# Wifi.net
KiCad netlist of a schematic drawn in Altium Designer
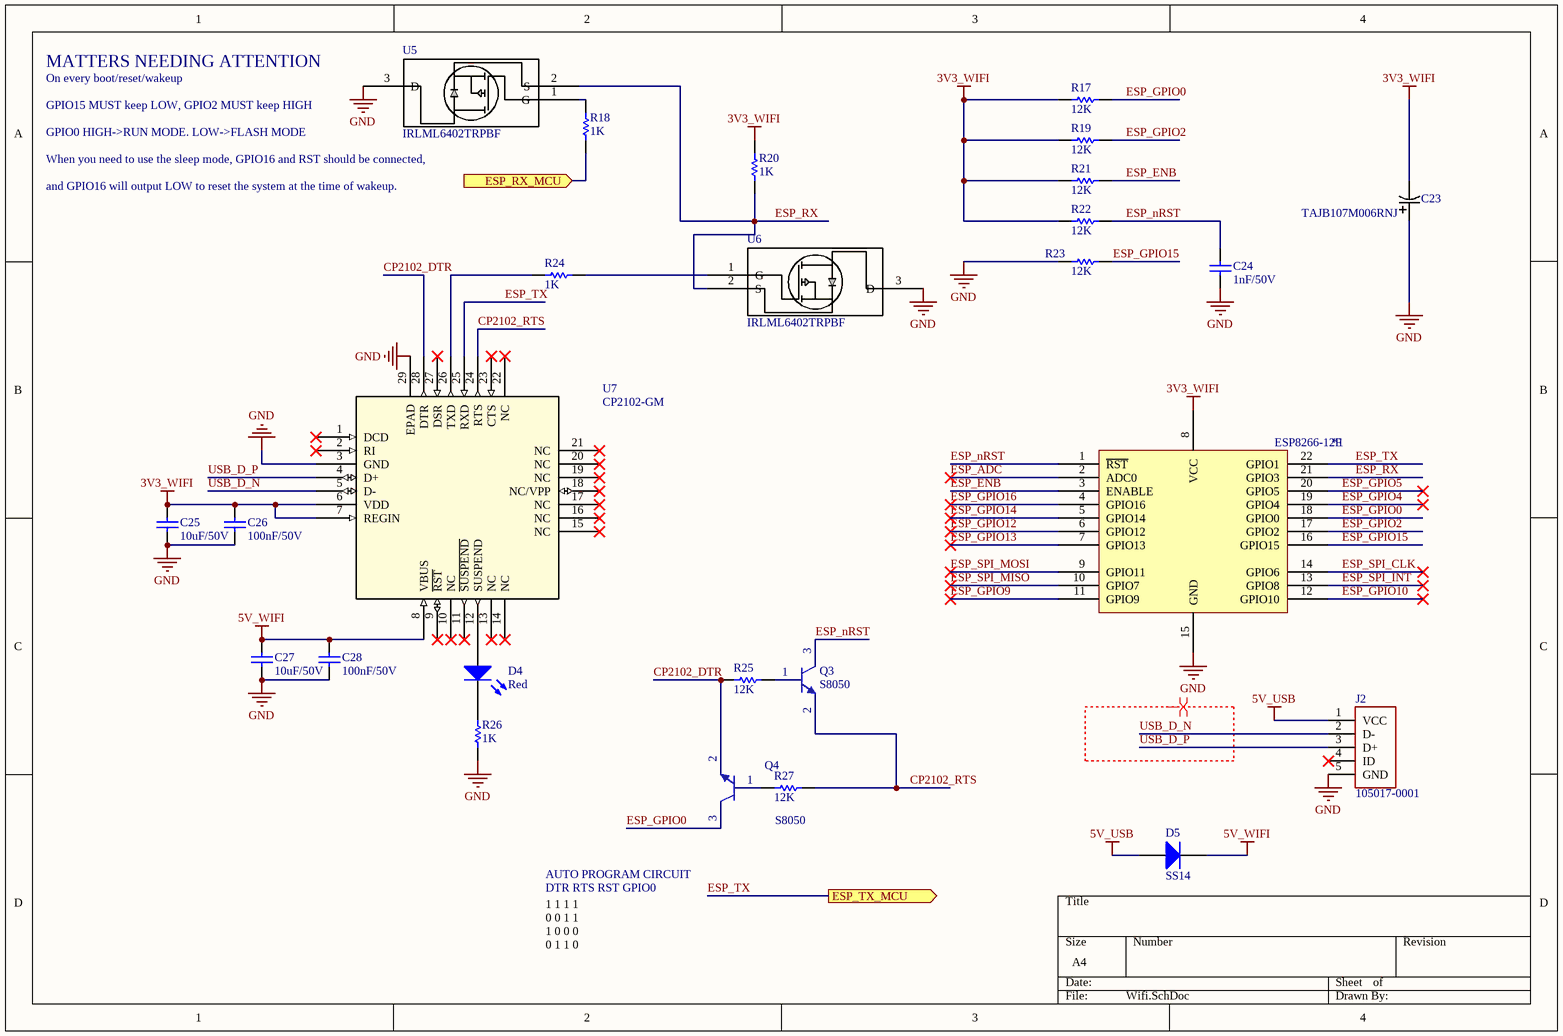
[diagram p0: Wifi.SchDoc]

(export (version "E")
  (design (tool "Eeschema 10.0.6"))
  (components
    (comp (ref "*1")
      (value "ESP8266-12F")
      (footprint "ESP8266")
      (libsource (lib "Schlib1") (part "ESP8266-12F"))
    )
    (comp (ref "C23")
      (value "TAJB107M006RNJ")
      (footprint "TAJB107M006RNJ")
      (fields (field (name "COPYRIGHT") "Copyright (C) 2018 Accelerated Designs. All rights reserved"))
      (libsource (lib "Integrated_Library") (part "TAJB107M006RNJ"))
    )
    (comp (ref "C24")
      (value "1nF/50V")
      (footprint "CAP-SM-0805")
      (description "CAP CER 1000PF 100V X7R 0805")
      (fields
        (field (name "MANUFACTURER") "Johanson Dielectrics Inc.")
        (field (name "MANUFACTURER PART NUMBER") "101X15W102MV4E")
      )
      (libsource (lib "Capacitor") (part "Cap-1nF-50V-0805"))
    )
    (comp (ref "C25")
      (value "10uF/50V")
      (footprint "CAP-SM-0805")
      (description "CAP CER 1000PF 100V X7R 0805")
      (fields
        (field (name "MANUFACTURER") "Johanson Dielectrics Inc.")
        (field (name "MANUFACTURER PART NUMBER") "101X15W102MV4E")
      )
      (libsource (lib "Capacitor") (part "Cap-1nF-50V-0805"))
    )
    (comp (ref "C26")
      (value "100nF/50V")
      (footprint "CAP-SM-0805")
      (description "CAP CER 1000PF 100V X7R 0805")
      (fields
        (field (name "MANUFACTURER") "Johanson Dielectrics Inc.")
        (field (name "MANUFACTURER PART NUMBER") "101X15W102MV4E")
      )
      (libsource (lib "Capacitor") (part "Cap-1nF-50V-0805"))
    )
    (comp (ref "C27")
      (value "10uF/50V")
      (footprint "CAP-SM-0805")
      (description "CAP CER 1000PF 100V X7R 0805")
      (fields
        (field (name "MANUFACTURER") "Johanson Dielectrics Inc.")
        (field (name "MANUFACTURER PART NUMBER") "101X15W102MV4E")
      )
      (libsource (lib "Capacitor") (part "Cap-1nF-50V-0805"))
    )
    (comp (ref "C28")
      (value "100nF/50V")
      (footprint "CAP-SM-0805")
      (description "CAP CER 1000PF 100V X7R 0805")
      (fields
        (field (name "MANUFACTURER") "Johanson Dielectrics Inc.")
        (field (name "MANUFACTURER PART NUMBER") "101X15W102MV4E")
      )
      (libsource (lib "Capacitor") (part "Cap-1nF-50V-0805"))
    )
    (comp (ref "D4")
      (value "Red")
      (footprint "LED-3mm")
      (description "LED RED CLEAR T-1 T/H")
      (fields
        (field (name "MANUFACTURER") "Kingbright")
        (field (name "MANUFACTURER PART NUMBER") "WP710A10SEC/J3")
      )
      (libsource (lib "LED") (part "LED-RED-TH-3mm"))
    )
    (comp (ref "D5")
      (value "SS14")
      (footprint "SS14")
      (description "DIODE SCHOTTKY 40V 1A SMA")
      (fields (field (name "MANUFACTURER") "ON Semiconductor"))
      (libsource (lib "Diode") (part "Diode-SS14"))
    )
    (comp (ref "J2")
      (value "105017-0001")
      (footprint "CONN_105017-0001")
      (description "No Description Available")
      (fields (field (name "COPYRIGHT") "Copyright (C) 2018 Accelerated Designs. All rights reserved"))
      (libsource (lib "Header-connector") (part "105017-0001"))
    )
    (comp (ref "Q3") (value "S8050") (footprint "SOT23_NEX") (libsource (lib "BJT") (part "S8050")))
    (comp (ref "Q4") (value "S8050") (footprint "SOT23_NEX") (libsource (lib "BJT") (part "S8050")))
    (comp (ref "R17")
      (value "12K")
      (footprint "Resistor:RES-SM-0805")
      (description "RES 0 OHM JUMPER 0805")
      (fields
        (field (name "MANUFACTURER") "Vishay Dale")
        (field (name "MANUFACTURER PART NUMBER") "WSL080500000ZEA9")
      )
      (libsource (lib "Resistor") (part "Res-0-0805"))
    )
    (comp (ref "R18")
      (value "1K")
      (footprint "Resistor:RES-SM-0805")
      (description "RES 470 OHM JUMPER 0805")
      (fields
        (field (name "MANUFACTURER") "YAG6006CT-ND")
        (field (name "MANUFACTURER PART NUMBER") "PE0805FRF7W0R047L")
      )
      (libsource (lib "Resistor") (part "Res-470-0805"))
    )
    (comp (ref "R19")
      (value "12K")
      (footprint "Resistor:RES-SM-0805")
      (description "RES 0 OHM JUMPER 0805")
      (fields
        (field (name "MANUFACTURER") "Vishay Dale")
        (field (name "MANUFACTURER PART NUMBER") "WSL080500000ZEA9")
      )
      (libsource (lib "Resistor") (part "Res-0-0805"))
    )
    (comp (ref "R20")
      (value "1K")
      (footprint "Resistor:RES-SM-0805")
      (description "RES 470 OHM JUMPER 0805")
      (fields
        (field (name "MANUFACTURER") "YAG6006CT-ND")
        (field (name "MANUFACTURER PART NUMBER") "PE0805FRF7W0R047L")
      )
      (libsource (lib "Resistor") (part "Res-470-0805"))
    )
    (comp (ref "R21")
      (value "12K")
      (footprint "Resistor:RES-SM-0805")
      (description "RES 0 OHM JUMPER 0805")
      (fields
        (field (name "MANUFACTURER") "Vishay Dale")
        (field (name "MANUFACTURER PART NUMBER") "WSL080500000ZEA9")
      )
      (libsource (lib "Resistor") (part "Res-0-0805"))
    )
    (comp (ref "R22")
      (value "12K")
      (footprint "Resistor:RES-SM-0805")
      (description "RES 0 OHM JUMPER 0805")
      (fields
        (field (name "MANUFACTURER") "Vishay Dale")
        (field (name "MANUFACTURER PART NUMBER") "WSL080500000ZEA9")
      )
      (libsource (lib "Resistor") (part "Res-0-0805"))
    )
    (comp (ref "R23")
      (value "12K")
      (footprint "Resistor:RES-SM-0805")
      (description "RES 0 OHM JUMPER 0805")
      (fields
        (field (name "MANUFACTURER") "Vishay Dale")
        (field (name "MANUFACTURER PART NUMBER") "WSL080500000ZEA9")
      )
      (libsource (lib "Resistor") (part "Res-0-0805"))
    )
    (comp (ref "R24")
      (value "1K")
      (footprint "Resistor:RES-SM-0805")
      (description "RES 470 OHM JUMPER 0805")
      (fields
        (field (name "MANUFACTURER") "YAG6006CT-ND")
        (field (name "MANUFACTURER PART NUMBER") "PE0805FRF7W0R047L")
      )
      (libsource (lib "Resistor") (part "Res-470-0805"))
    )
    (comp (ref "R25")
      (value "12K")
      (footprint "Resistor:RES-SM-0805")
      (description "RES 0 OHM JUMPER 0805")
      (fields
        (field (name "MANUFACTURER") "Vishay Dale")
        (field (name "MANUFACTURER PART NUMBER") "WSL080500000ZEA9")
      )
      (libsource (lib "Resistor") (part "Res-0-0805"))
    )
    (comp (ref "R26")
      (value "1K")
      (footprint "Resistor:RES-SM-0805")
      (description "RES 470 OHM JUMPER 0805")
      (fields
        (field (name "MANUFACTURER") "YAG6006CT-ND")
        (field (name "MANUFACTURER PART NUMBER") "PE0805FRF7W0R047L")
      )
      (libsource (lib "Resistor") (part "Res-470-0805"))
    )
    (comp (ref "R27")
      (value "12K")
      (footprint "Resistor:RES-SM-0805")
      (description "RES 0 OHM JUMPER 0805")
      (fields
        (field (name "MANUFACTURER") "Vishay Dale")
        (field (name "MANUFACTURER PART NUMBER") "WSL080500000ZEA9")
      )
      (libsource (lib "Resistor") (part "Res-0-0805"))
    )
    (comp (ref "U5")
      (value "IRLML6402TRPBF")
      (footprint "IRLML6402TRPBF")
      (description "No Description Available")
      (fields (field (name "COPYRIGHT") "Copyright (C) 2018 Accelerated Designs. All rights reserved"))
      (libsource (lib "Integrated_Library") (part "IRLML6402TRPBF"))
    )
    (comp (ref "U6")
      (value "IRLML6402TRPBF")
      (footprint "IRLML6402TRPBF")
      (description "No Description Available")
      (fields (field (name "COPYRIGHT") "Copyright (C) 2018 Accelerated Designs. All rights reserved"))
      (libsource (lib "Integrated_Library") (part "IRLML6402TRPBF"))
    )
    (comp (ref "U7")
      (value "CP2102-GM")
      (footprint "cp2102-gm")
      (fields (field (name "COPYRIGHT") "Copyright (C) 2018 Accelerated Designs. All rights reserved"))
      (libsource (lib "Schlib1") (part "CP2102-GM"))
    )
  )
  (nets
    (net (code "1") (name "/CP2102_DTR") (class "Default")
      (node (ref "Q4") (pin "2") (pinfunction "E_2") (pintype "passive"))
      (node (ref "R25") (pin "1") (pinfunction "1_1") (pintype "passive"))
      (node (ref "U7") (pin "28") (pinfunction "DTR_28") (pintype "output"))
    )
    (net (code "2") (name "/CP2102_RTS") (class "Default")
      (node (ref "Q3") (pin "2") (pinfunction "E_2") (pintype "passive"))
      (node (ref "R27") (pin "2") (pinfunction "2_2") (pintype "passive"))
      (node (ref "U7") (pin "24") (pinfunction "RTS_24") (pintype "output"))
    )
    (net (code "3") (name "/ESP_ADC") (class "Default")
      (node (ref "*1") (pin "2") (pinfunction "ADC0_2") (pintype "passive+no_connect"))
    )
    (net (code "4") (name "/ESP_ENB") (class "Default")
      (node (ref "*1") (pin "3") (pinfunction "ENABLE_3") (pintype "passive"))
      (node (ref "R21") (pin "2") (pinfunction "2_2") (pintype "passive"))
    )
    (net (code "5") (name "/ESP_GPIO0") (class "Default")
      (node (ref "*1") (pin "18") (pinfunction "GPIO0_18") (pintype "passive"))
      (node (ref "Q4") (pin "3") (pinfunction "C_3") (pintype "passive"))
      (node (ref "R17") (pin "2") (pinfunction "2_2") (pintype "passive"))
    )
    (net (code "6") (name "/ESP_GPIO2") (class "Default")
      (node (ref "*1") (pin "17") (pinfunction "GPIO2_17") (pintype "passive"))
      (node (ref "R19") (pin "2") (pinfunction "2_2") (pintype "passive"))
    )
    (net (code "7") (name "/ESP_GPIO4") (class "Default")
      (node (ref "*1") (pin "19") (pinfunction "GPIO4_19") (pintype "passive+no_connect"))
    )
    (net (code "8") (name "/ESP_GPIO5") (class "Default")
      (node (ref "*1") (pin "20") (pinfunction "GPIO5_20") (pintype "passive+no_connect"))
    )
    (net (code "9") (name "/ESP_GPIO9") (class "Default")
      (node (ref "*1") (pin "11") (pinfunction "GPIO9_11") (pintype "passive+no_connect"))
    )
    (net (code "10") (name "/ESP_GPIO10") (class "Default")
      (node (ref "*1") (pin "12") (pinfunction "GPIO10_12") (pintype "passive+no_connect"))
    )
    (net (code "11") (name "/ESP_GPIO12") (class "Default")
      (node (ref "*1") (pin "6") (pinfunction "GPIO12_6") (pintype "passive+no_connect"))
    )
    (net (code "12") (name "/ESP_GPIO13") (class "Default")
      (node (ref "*1") (pin "7") (pinfunction "GPIO13_7") (pintype "passive+no_connect"))
    )
    (net (code "13") (name "/ESP_GPIO14") (class "Default")
      (node (ref "*1") (pin "5") (pinfunction "GPIO14_5") (pintype "passive+no_connect"))
    )
    (net (code "14") (name "/ESP_GPIO15") (class "Default")
      (node (ref "*1") (pin "16") (pinfunction "GPIO15_16") (pintype "passive"))
      (node (ref "R23") (pin "2") (pinfunction "2_2") (pintype "passive"))
    )
    (net (code "15") (name "/ESP_GPIO16") (class "Default")
      (node (ref "*1") (pin "4") (pinfunction "GPIO16_4") (pintype "passive+no_connect"))
    )
    (net (code "16") (name "/ESP_RX") (class "Default")
      (node (ref "*1") (pin "21") (pinfunction "GPIO3_21") (pintype "passive"))
      (node (ref "R20") (pin "2") (pinfunction "2_2") (pintype "passive"))
      (node (ref "U5") (pin "2") (pinfunction "S_2") (pintype "passive"))
      (node (ref "U6") (pin "2") (pinfunction "S_2") (pintype "passive"))
    )
    (net (code "17") (name "/ESP_RX_MCU") (class "Default")
      (node (ref "R18") (pin "1") (pinfunction "1_1") (pintype "passive"))
    )
    (net (code "18") (name "/ESP_SPI_CLK") (class "Default")
      (node (ref "*1") (pin "14") (pinfunction "GPIO6_14") (pintype "passive+no_connect"))
    )
    (net (code "19") (name "/ESP_SPI_INT") (class "Default")
      (node (ref "*1") (pin "13") (pinfunction "GPIO8_13") (pintype "passive+no_connect"))
    )
    (net (code "20") (name "/ESP_SPI_MISO") (class "Default")
      (node (ref "*1") (pin "10") (pinfunction "GPIO7_10") (pintype "passive+no_connect"))
    )
    (net (code "21") (name "/ESP_SPI_MOSI") (class "Default")
      (node (ref "*1") (pin "9") (pinfunction "GPIO11_9") (pintype "passive+no_connect"))
    )
    (net (code "22") (name "/ESP_TX") (class "Default")
      (node (ref "*1") (pin "22") (pinfunction "GPIO1_22") (pintype "passive"))
      (node (ref "U7") (pin "25") (pinfunction "RXD_25") (pintype "input"))
    )
    (net (code "23") (name "/ESP_nRST") (class "Default")
      (node (ref "*1") (pin "1") (pinfunction "~{RST}_1") (pintype "passive"))
      (node (ref "C24") (pin "2") (pinfunction "2_2") (pintype "passive"))
      (node (ref "Q3") (pin "3") (pinfunction "C_3") (pintype "passive"))
      (node (ref "R22") (pin "2") (pinfunction "2_2") (pintype "passive"))
    )
    (net (code "24") (name "/USB_D_N") (class "Default")
      (node (ref "J2") (pin "2") (pinfunction "D-_2") (pintype "passive"))
      (node (ref "U7") (pin "5") (pinfunction "D-_5") (pintype "bidirectional"))
    )
    (net (code "25") (name "/USB_D_P") (class "Default")
      (node (ref "J2") (pin "3") (pinfunction "D+_3") (pintype "passive"))
      (node (ref "U7") (pin "4") (pinfunction "D+_4") (pintype "bidirectional"))
    )
    (net (code "26") (name "3V3_WIFI") (class "Default")
      (node (ref "*1") (pin "8") (pinfunction "VCC_8") (pintype "passive"))
      (node (ref "C23") (pin "2") (pinfunction "12_2") (pintype "passive"))
      (node (ref "C25") (pin "2") (pinfunction "2_2") (pintype "passive"))
      (node (ref "C26") (pin "2") (pinfunction "2_2") (pintype "passive"))
      (node (ref "R17") (pin "1") (pinfunction "1_1") (pintype "passive"))
      (node (ref "R19") (pin "1") (pinfunction "1_1") (pintype "passive"))
      (node (ref "R20") (pin "1") (pinfunction "1_1") (pintype "passive"))
      (node (ref "R21") (pin "1") (pinfunction "1_1") (pintype "passive"))
      (node (ref "R22") (pin "1") (pinfunction "1_1") (pintype "passive"))
      (node (ref "U7") (pin "6") (pinfunction "VDD_6") (pintype "power_in"))
      (node (ref "U7") (pin "7") (pinfunction "REGIN_7") (pintype "input"))
    )
    (net (code "27") (name "5V_USB") (class "Default")
      (node (ref "D5") (pin "2") (pinfunction "A_2") (pintype "passive"))
      (node (ref "J2") (pin "1") (pinfunction "VCC_1") (pintype "passive"))
    )
    (net (code "28") (name "5V_WIFI") (class "Default")
      (node (ref "C27") (pin "2") (pinfunction "2_2") (pintype "passive"))
      (node (ref "C28") (pin "2") (pinfunction "2_2") (pintype "passive"))
      (node (ref "D5") (pin "1") (pinfunction "K_1") (pintype "passive"))
      (node (ref "U7") (pin "8") (pinfunction "VBUS_8") (pintype "input"))
    )
    (net (code "29") (name "GND") (class "Default")
      (node (ref "*1") (pin "15") (pinfunction "GND_15") (pintype "passive"))
      (node (ref "C23") (pin "1") (pinfunction "11_1") (pintype "passive"))
      (node (ref "C24") (pin "1") (pinfunction "1_1") (pintype "passive"))
      (node (ref "C25") (pin "1") (pinfunction "1_1") (pintype "passive"))
      (node (ref "C26") (pin "1") (pinfunction "1_1") (pintype "passive"))
      (node (ref "C27") (pin "1") (pinfunction "1_1") (pintype "passive"))
      (node (ref "C28") (pin "1") (pinfunction "1_1") (pintype "passive"))
      (node (ref "J2") (pin "5") (pinfunction "GND_5") (pintype "passive"))
      (node (ref "R23") (pin "1") (pinfunction "1_1") (pintype "passive"))
      (node (ref "R26") (pin "1") (pinfunction "1_1") (pintype "passive"))
      (node (ref "U5") (pin "3") (pinfunction "D_3") (pintype "passive"))
      (node (ref "U6") (pin "3") (pinfunction "D_3") (pintype "passive"))
      (node (ref "U7") (pin "29") (pinfunction "EPAD_29") (pintype "passive"))
      (node (ref "U7") (pin "3") (pinfunction "GND_3") (pintype "power_in"))
    )
    (net (code "30") (name "Net-(D4-A)") (class "Default")
      (node (ref "D4") (pin "1") (pinfunction "A_1") (pintype "passive"))
      (node (ref "U7") (pin "12") (pinfunction "SUSPEND_12") (pintype "output"))
    )
    (net (code "31") (name "Net-(D4-K)") (class "Default")
      (node (ref "D4") (pin "2") (pinfunction "K_2") (pintype "passive"))
      (node (ref "R26") (pin "2") (pinfunction "2_2") (pintype "passive"))
    )
    (net (code "32") (name "Net-(Q3-B)") (class "Default")
      (node (ref "Q3") (pin "1") (pinfunction "B_1") (pintype "passive"))
      (node (ref "R25") (pin "2") (pinfunction "2_2") (pintype "passive"))
    )
    (net (code "33") (name "Net-(Q4-B)") (class "Default")
      (node (ref "Q4") (pin "1") (pinfunction "B_1") (pintype "passive"))
      (node (ref "R27") (pin "1") (pinfunction "1_1") (pintype "passive"))
    )
    (net (code "34") (name "Net-(U5-G)") (class "Default")
      (node (ref "R18") (pin "2") (pinfunction "2_2") (pintype "passive"))
      (node (ref "U5") (pin "1") (pinfunction "G_1") (pintype "passive"))
    )
    (net (code "35") (name "Net-(U6-G)") (class "Default")
      (node (ref "R24") (pin "1") (pinfunction "1_1") (pintype "passive"))
      (node (ref "U6") (pin "1") (pinfunction "G_1") (pintype "passive"))
    )
    (net (code "36") (name "Net-(U7-TXD)") (class "Default")
      (node (ref "R24") (pin "2") (pinfunction "2_2") (pintype "passive"))
      (node (ref "U7") (pin "26") (pinfunction "TXD_26") (pintype "output"))
    )
    (net (code "37") (name "unconnected-(J2-ID-Pad4)") (class "Default")
      (node (ref "J2") (pin "4") (pinfunction "ID_4") (pintype "passive+no_connect"))
    )
    (net (code "38") (name "unconnected-(U7-CTS-Pad23)") (class "Default")
      (node (ref "U7") (pin "23") (pinfunction "CTS_23") (pintype "input+no_connect"))
    )
    (net (code "39") (name "unconnected-(U7-DCD-Pad1)") (class "Default")
      (node (ref "U7") (pin "1") (pinfunction "DCD_1") (pintype "input+no_connect"))
    )
    (net (code "40") (name "unconnected-(U7-DSR-Pad27)") (class "Default")
      (node (ref "U7") (pin "27") (pinfunction "DSR_27") (pintype "input+no_connect"))
    )
    (net (code "41") (name "unconnected-(U7-NC-Pad10)") (class "Default")
      (node (ref "U7") (pin "10") (pinfunction "NC_10") (pintype "passive+no_connect"))
    )
    (net (code "42") (name "unconnected-(U7-NC-Pad13)") (class "Default")
      (node (ref "U7") (pin "13") (pinfunction "NC_13") (pintype "passive+no_connect"))
    )
    (net (code "43") (name "unconnected-(U7-NC-Pad14)") (class "Default")
      (node (ref "U7") (pin "14") (pinfunction "NC_14") (pintype "passive+no_connect"))
    )
    (net (code "44") (name "unconnected-(U7-NC-Pad15)") (class "Default")
      (node (ref "U7") (pin "15") (pinfunction "NC_15") (pintype "passive+no_connect"))
    )
    (net (code "45") (name "unconnected-(U7-NC-Pad16)") (class "Default")
      (node (ref "U7") (pin "16") (pinfunction "NC_16") (pintype "passive+no_connect"))
    )
    (net (code "46") (name "unconnected-(U7-NC-Pad17)") (class "Default")
      (node (ref "U7") (pin "17") (pinfunction "NC_17") (pintype "passive+no_connect"))
    )
    (net (code "47") (name "unconnected-(U7-NC-Pad19)") (class "Default")
      (node (ref "U7") (pin "19") (pinfunction "NC_19") (pintype "passive+no_connect"))
    )
    (net (code "48") (name "unconnected-(U7-NC-Pad20)") (class "Default")
      (node (ref "U7") (pin "20") (pinfunction "NC_20") (pintype "passive+no_connect"))
    )
    (net (code "49") (name "unconnected-(U7-NC-Pad21)") (class "Default")
      (node (ref "U7") (pin "21") (pinfunction "NC_21") (pintype "passive+no_connect"))
    )
    (net (code "50") (name "unconnected-(U7-NC-Pad22)") (class "Default")
      (node (ref "U7") (pin "22") (pinfunction "NC_22") (pintype "passive+no_connect"))
    )
    (net (code "51") (name "unconnected-(U7-NC{slash}VPP-Pad18)") (class "Default")
      (node (ref "U7") (pin "18") (pinfunction "NC/VPP_18") (pintype "bidirectional+no_connect"))
    )
    (net (code "52") (name "unconnected-(U7-RI-Pad2)") (class "Default")
      (node (ref "U7") (pin "2") (pinfunction "RI_2") (pintype "input+no_connect"))
    )
    (net (code "53") (name "unconnected-(U7-~{RST}-Pad9)") (class "Default")
      (node (ref "U7") (pin "9") (pinfunction "~{RST}_9") (pintype "bidirectional+no_connect"))
    )
    (net (code "54") (name "unconnected-(U7-~{SUSPEND}-Pad11)") (class "Default")
      (node (ref "U7") (pin "11") (pinfunction "~{SUSPEND}_11") (pintype "output+no_connect"))
    )
  )
)
